# twibby.net
KiCad netlist of a schematic drawn in EasyEDA Pro
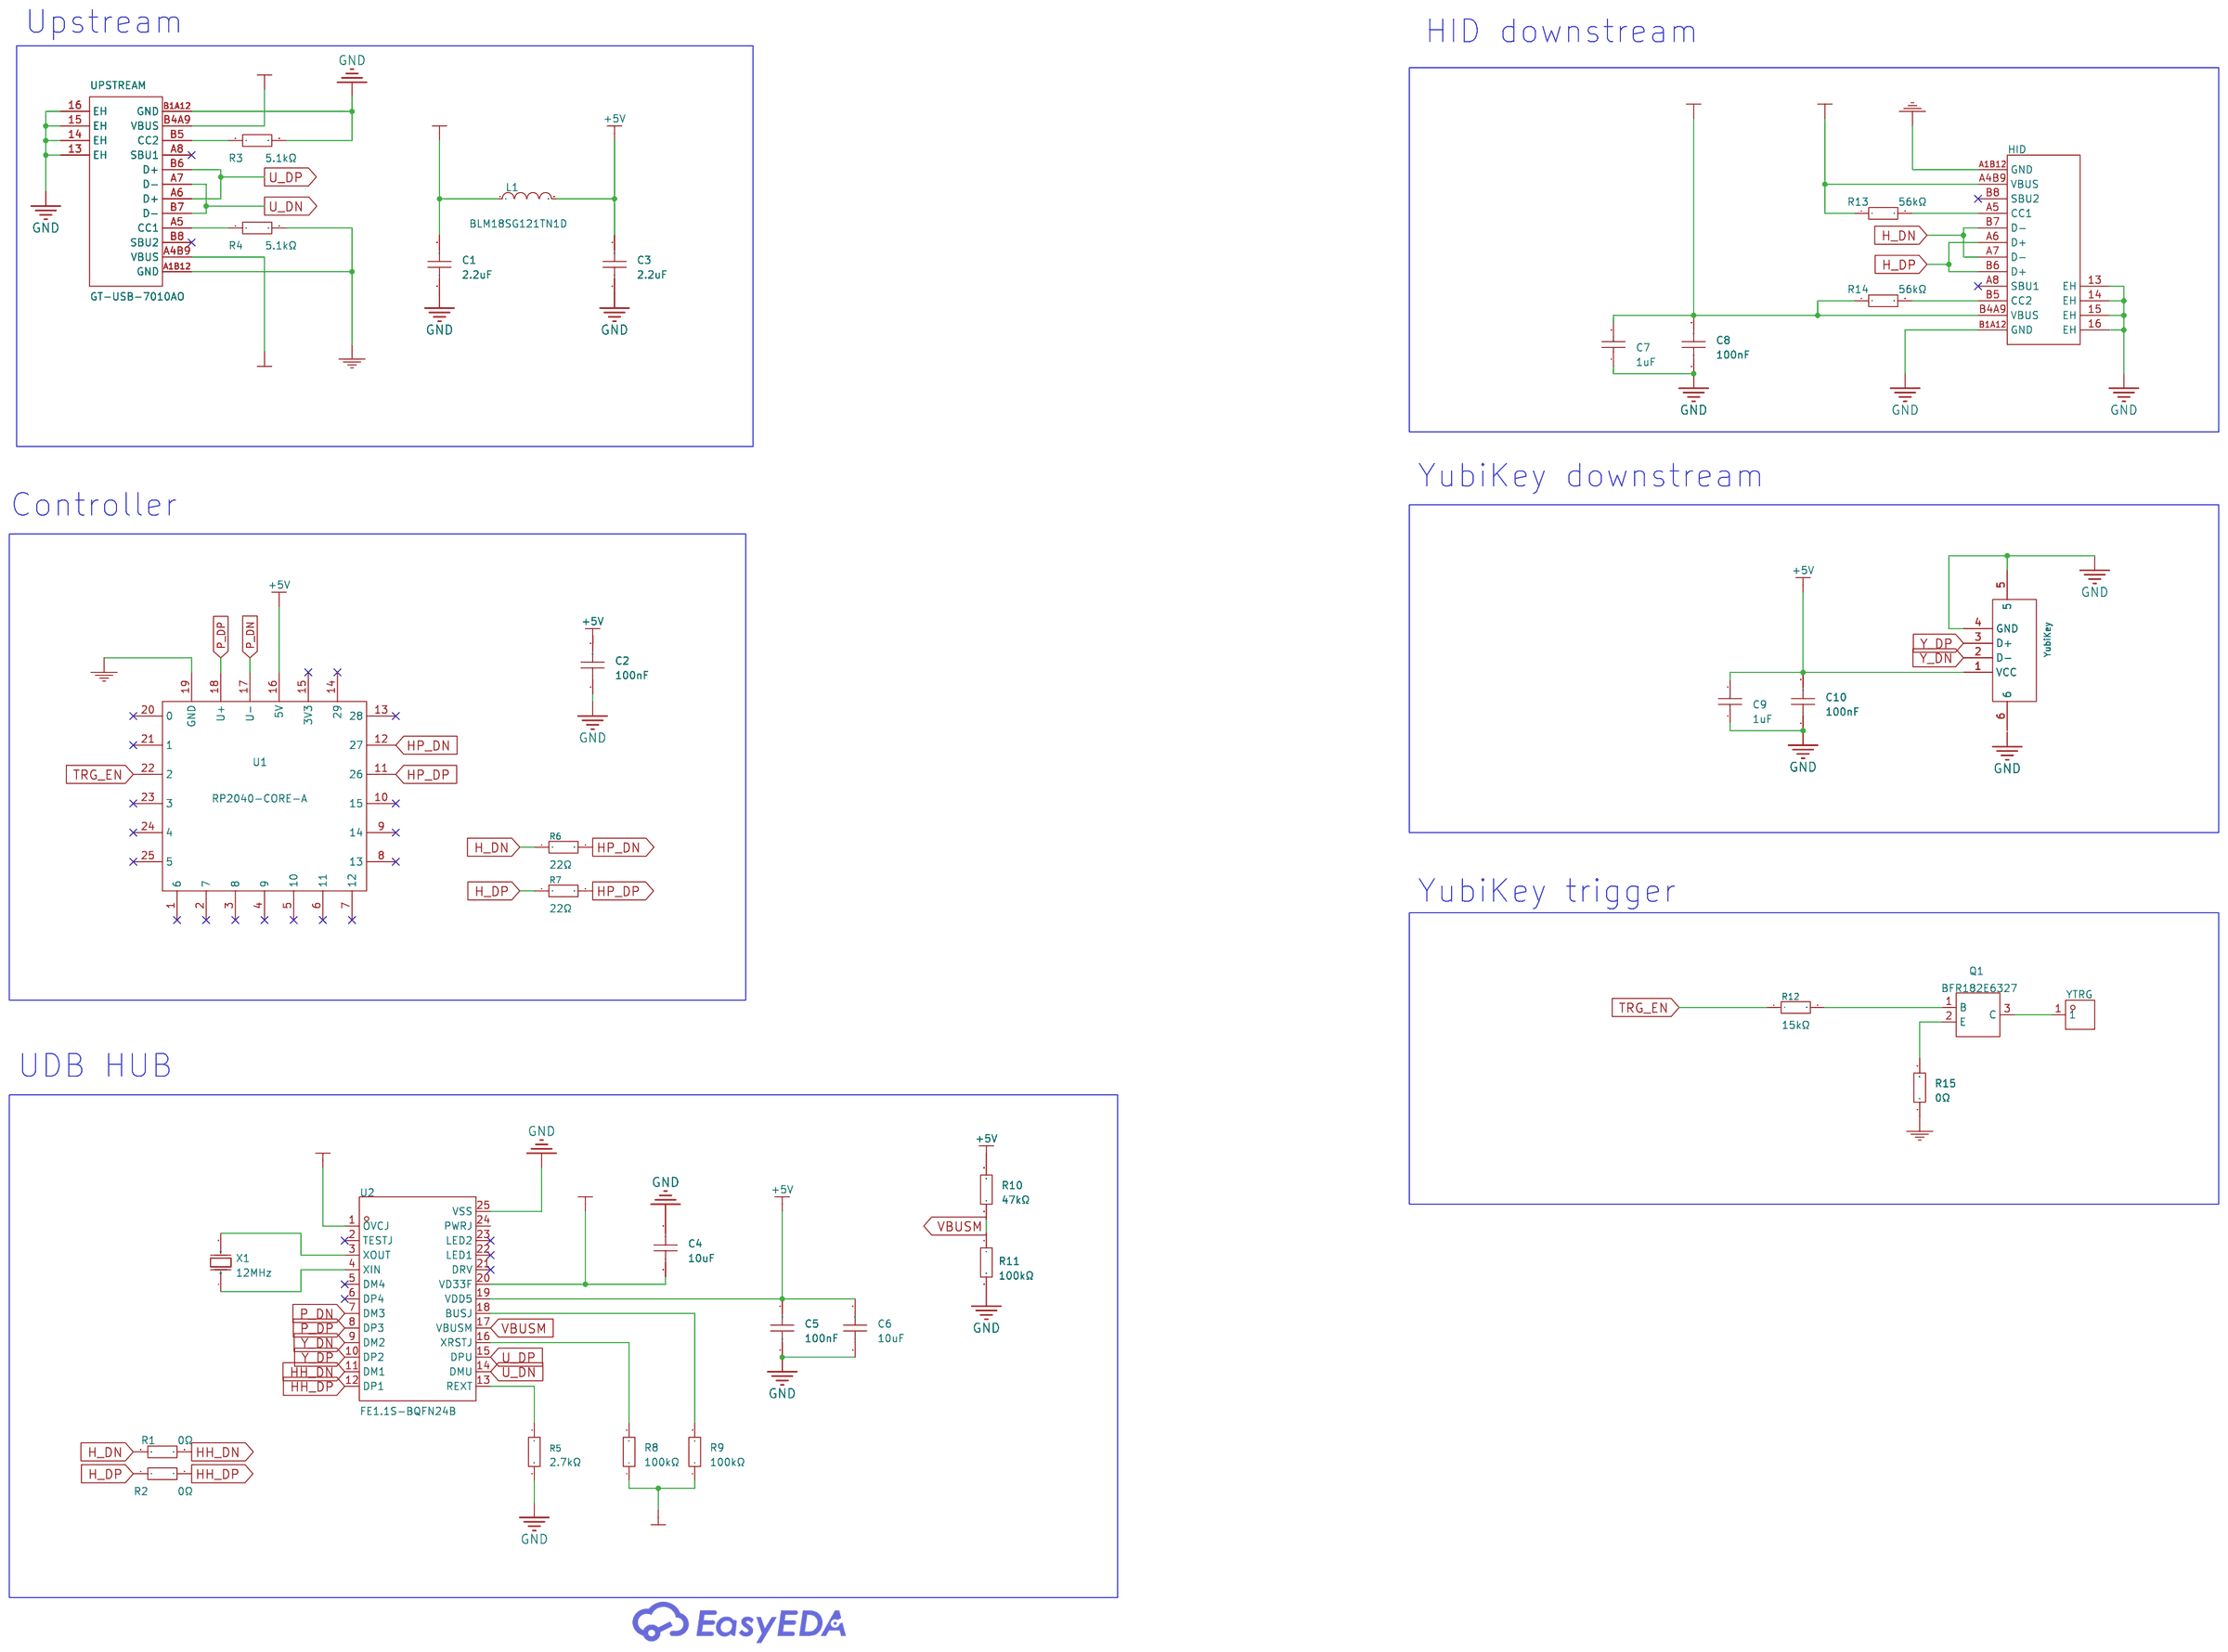
[diagram p0: schematic sheet]

(export (version "E")
  (design (tool "Eeschema 10.0.6"))
  (components
    (comp (ref "C1")
      (value "2.2uF")
      (fields
        (field (name "Manufacturer Part") "CL21A225KBQNNNE")
        (field (name "Manufacturer") "SAMSUNG(三星)")
      )
      (libsource (lib "easyedapro") (part "GRM188Z71E225KE43D"))
    )
    (comp (ref "C2")
      (value "100nF")
      (fields
        (field (name "Manufacturer Part") "CL21B104KCFNNNE")
        (field (name "Manufacturer") "SAMSUNG(三星)")
      )
      (libsource (lib "easyedapro") (part "CL21B104KBFWPJE"))
    )
    (comp (ref "C3")
      (value "2.2uF")
      (fields
        (field (name "Manufacturer Part") "CL21A225KBQNNNE")
        (field (name "Manufacturer") "SAMSUNG(三星)")
      )
      (libsource (lib "easyedapro") (part "GRM188Z71E225KE43D"))
    )
    (comp (ref "C4")
      (value "10uF")
      (footprint "easyedapro:C0603")
      (fields
        (field (name "Manufacturer Part") "CL10A106KP8NNNC")
        (field (name "Manufacturer") "SAMSUNG(三星)")
      )
      (libsource (lib "easyedapro") (part "CL10A106KP8NNNC"))
    )
    (comp (ref "C5")
      (value "100nF")
      (footprint "easyedapro:C0402")
      (fields
        (field (name "Manufacturer Part") "CL05B104KO5NNNC")
        (field (name "Manufacturer") "SAMSUNG(三星)")
      )
      (libsource (lib "easyedapro") (part "100nF"))
    )
    (comp (ref "C6")
      (value "10uF")
      (footprint "easyedapro:C0603")
      (fields
        (field (name "Manufacturer Part") "CL10A106KP8NNNC")
        (field (name "Manufacturer") "SAMSUNG(三星)")
      )
      (libsource (lib "easyedapro") (part "CL10A106KP8NNNC"))
    )
    (comp (ref "C7")
      (value "1uF")
      (description "Capacitance:1uF Tolerance:±10% Tolerance:±10% Voltage Rating:50V Temperature Coefficient:X7R")
      (fields (field (name "Manufacturer Part") "0805B105K500NT") (field (name "Manufacturer") "FH(风华)"))
      (libsource (lib "easyedapro") (part "CL21B105KAFNNNE"))
    )
    (comp (ref "C8")
      (value "100nF")
      (fields
        (field (name "Manufacturer Part") "CL21B104KCFNNNE")
        (field (name "Manufacturer") "SAMSUNG(三星)")
      )
      (libsource (lib "easyedapro") (part "CL21B104KBFWPJE"))
    )
    (comp (ref "C9")
      (value "1uF")
      (description "Capacitance:1uF Tolerance:±10% Tolerance:±10% Voltage Rating:50V Temperature Coefficient:X7R")
      (fields (field (name "Manufacturer Part") "0805B105K500NT") (field (name "Manufacturer") "FH(风华)"))
      (libsource (lib "easyedapro") (part "CL21B105KAFNNNE"))
    )
    (comp (ref "C10")
      (value "100nF")
      (fields
        (field (name "Manufacturer Part") "CL21B104KCFNNNE")
        (field (name "Manufacturer") "SAMSUNG(三星)")
      )
      (libsource (lib "easyedapro") (part "CL21B104KBFWPJE"))
    )
    (comp (ref "HID")
      (value "GT-USB-7010AO")
      (footprint "easyedapro:USB-C-SMD_TYPEC-304J-BCP16")
      (fields (field (name "Manufacturer") "G-Switch(品赞)"))
      (libsource (lib "easyedapro") (part "GT-USB-7010AO"))
    )
    (comp (ref "L1")
      (value "BLM18SG121TN1D")
      (footprint "easyedapro:L0603")
      (fields (field (name "Manufacturer") "muRata(村田)"))
      (libsource (lib "easyedapro") (part "BLM18SG121TN1D"))
    )
    (comp (ref "Q1")
      (value "BFR182E6327")
      (footprint "easyedapro:SOT-23-3_L2.9-W1.3-P1.90-LS2.4-BR")
      (fields (field (name "Manufacturer") "Infineon(英飞凌)") (field (name "Contributor") "LCSC"))
      (libsource (lib "easyedapro") (part "BFR182E6327"))
    )
    (comp (ref "R1")
      (value "0Ω")
      (footprint "easyedapro:R0603")
      (fields
        (field (name "Manufacturer Part") "0603WAF0000T5E")
        (field (name "Manufacturer") "UNI-ROYAL(厚声)")
      )
      (libsource (lib "easyedapro") (part "0603WAF0000T5E"))
    )
    (comp (ref "R2")
      (value "0Ω")
      (footprint "easyedapro:R0603")
      (fields
        (field (name "Manufacturer Part") "0603WAF0000T5E")
        (field (name "Manufacturer") "UNI-ROYAL(厚声)")
      )
      (libsource (lib "easyedapro") (part "0603WAF0000T5E"))
    )
    (comp (ref "R3")
      (value "5.1kΩ")
      (footprint "easyedapro:R0402")
      (fields
        (field (name "Manufacturer Part") "0402WGF5101TCE")
        (field (name "Manufacturer") "UNI-ROYAL(厚声)")
      )
      (libsource (lib "easyedapro") (part "5.1kΩ"))
    )
    (comp (ref "R4")
      (value "5.1kΩ")
      (footprint "easyedapro:R0402")
      (fields
        (field (name "Manufacturer Part") "0402WGF5101TCE")
        (field (name "Manufacturer") "UNI-ROYAL(厚声)")
      )
      (libsource (lib "easyedapro") (part "5.1kΩ"))
    )
    (comp (ref "R5")
      (value "2.7kΩ")
      (fields
        (field (name "Manufacturer Part") "0603WAF2701T5E")
        (field (name "Manufacturer") "UNI-ROYAL(厚声)")
      )
      (libsource (lib "easyedapro") (part "0402WGF2701TCE"))
    )
    (comp (ref "R6")
      (value "22Ω")
      (footprint "easyedapro:R0402")
      (fields
        (field (name "Manufacturer Part") "0402WGF220JTCE")
        (field (name "Manufacturer") "UNI-ROYAL(厚声)")
      )
      (libsource (lib "easyedapro") (part "0402WGF220JTCE"))
    )
    (comp (ref "R7")
      (value "22Ω")
      (footprint "easyedapro:R0402")
      (fields
        (field (name "Manufacturer Part") "0402WGF220JTCE")
        (field (name "Manufacturer") "UNI-ROYAL(厚声)")
      )
      (libsource (lib "easyedapro") (part "0402WGF220JTCE"))
    )
    (comp (ref "R8")
      (value "100kΩ")
      (footprint "easyedapro:R0402")
      (fields
        (field (name "Manufacturer Part") "0402WGF1003TCE")
        (field (name "Manufacturer") "UNI-ROYAL(厚声)")
      )
      (libsource (lib "easyedapro") (part "100kΩ"))
    )
    (comp (ref "R9")
      (value "100kΩ")
      (footprint "easyedapro:R0402")
      (fields
        (field (name "Manufacturer Part") "0402WGF1003TCE")
        (field (name "Manufacturer") "UNI-ROYAL(厚声)")
      )
      (libsource (lib "easyedapro") (part "100kΩ"))
    )
    (comp (ref "R10")
      (value "47kΩ")
      (footprint "easyedapro:R0402")
      (fields
        (field (name "Manufacturer Part") "0402WGF4702TCE")
        (field (name "Manufacturer") "UNI-ROYAL(厚声)")
      )
      (libsource (lib "easyedapro") (part "0402WGF4702TCE"))
    )
    (comp (ref "R11")
      (value "100kΩ")
      (footprint "easyedapro:R0402")
      (fields
        (field (name "Manufacturer Part") "0402WGF1003TCE")
        (field (name "Manufacturer") "UNI-ROYAL(厚声)")
      )
      (libsource (lib "easyedapro") (part "100kΩ"))
    )
    (comp (ref "R12")
      (value "15kΩ")
      (fields
        (field (name "Manufacturer Part") "0603WAF1502T5E")
        (field (name "Manufacturer") "UNI-ROYAL(厚声)")
      )
      (libsource (lib "easyedapro") (part "0402WGF1502TCE"))
    )
    (comp (ref "R13")
      (value "56kΩ")
      (fields
        (field (name "Manufacturer Part") "0603WAF5602T5E")
        (field (name "Manufacturer") "UNI-ROYAL(厚声)")
      )
      (libsource (lib "easyedapro") (part "0402WGF5602TCE"))
    )
    (comp (ref "R14")
      (value "56kΩ")
      (fields
        (field (name "Manufacturer Part") "0603WAF5602T5E")
        (field (name "Manufacturer") "UNI-ROYAL(厚声)")
      )
      (libsource (lib "easyedapro") (part "0402WGF5602TCE"))
    )
    (comp (ref "R15")
      (value "0Ω")
      (footprint "easyedapro:R0603")
      (fields
        (field (name "Manufacturer Part") "0603WAF0000T5E")
        (field (name "Manufacturer") "UNI-ROYAL(厚声)")
      )
      (libsource (lib "easyedapro") (part "0Ω"))
    )
    (comp (ref "U1")
      (value "RP2040-CORE-A")
      (footprint "easyedapro:RP2040-CORE-A")
      (fields (field (name "Contributor") "leeklabsinternational"))
      (libsource (lib "easyedapro") (part "RP2040-CORE-A"))
    )
    (comp (ref "U2")
      (value "FE1.1S-BQFN24B")
      (footprint "easyedapro:WQFN-24_L4.0-W4.0-P0.50-TL-EP2.7")
      (fields (field (name "Manufacturer") "TERMINUS"))
      (libsource (lib "easyedapro") (part "FE1.1S-BQFN24B"))
    )
    (comp (ref "UPSTREAM")
      (value "GT-USB-7010AO")
      (footprint "easyedapro:USB-C-SMD_TYPEC-304J-BCP16")
      (fields (field (name "Manufacturer") "G-Switch(品赞)"))
      (libsource (lib "easyedapro") (part "GT-USB-7010AO"))
    )
    (comp (ref "X1")
      (value "12MHz")
      (footprint "easyedapro:OSC-SMD_L5.0-W3.2")
      (fields (field (name "Manufacturer Part") "TAXM12M2QLFCDT1T") (field (name "Manufacturer") "YJX(雅晶鑫)"))
      (libsource (lib "easyedapro") (part "SMD-5032_2P 12M 20pf 30ppm"))
    )
    (comp (ref "YTRG")
      (value "5017")
      (footprint "easyedapro:CONN-SMD_5017")
      (libsource (lib "easyedapro") (part "5017_C9900015874"))
    )
    (comp (ref "YubiKey")
      (value "912-121A2026S10100")
      (footprint "easyedapro:USB-A-TH_C42425")
      (description "Connector Type:Type-A Standard:USB 2.0 Gender:Female Number of Ports:1 Number of Contacts:4P")
      (fields (field (name "Manufacturer") "精拓金"))
      (libsource (lib "easyedapro") (part "JTJ-USB-AF-90-10.6X13.1-H5.7-002"))
    )
  )
  (nets
    (net (code "1") (name "+3V3") (class "Default")
      (node (ref "C4") (pin "1") (pinfunction "1_1") (pintype "unspecified"))
      (node (ref "R8") (pin "1") (pinfunction "1_1") (pintype "input"))
      (node (ref "R9") (pin "1") (pinfunction "1_1") (pintype "input"))
      (node (ref "U2") (pin "1") (pinfunction "OVCJ_1") (pintype "unspecified"))
      (node (ref "U2") (pin "20") (pinfunction "VD33F_20") (pintype "unspecified"))
    )
    (net (code "2") (name "+5V") (class "Default")
      (node (ref "C10") (pin "2") (pinfunction "2_2") (pintype "unspecified"))
      (node (ref "C2") (pin "2") (pinfunction "2_2") (pintype "unspecified"))
      (node (ref "C3") (pin "2") (pinfunction "2_2") (pintype "unspecified"))
      (node (ref "C5") (pin "2") (pinfunction "2_2") (pintype "unspecified"))
      (node (ref "C6") (pin "2") (pinfunction "2_2") (pintype "unspecified"))
      (node (ref "C7") (pin "2") (pinfunction "2_2") (pintype "input"))
      (node (ref "C8") (pin "2") (pinfunction "2_2") (pintype "unspecified"))
      (node (ref "C9") (pin "2") (pinfunction "2_2") (pintype "input"))
      (node (ref "HID") (pin "A4B9") (pinfunction "VBUS_A4B9") (pintype "unspecified"))
      (node (ref "HID") (pin "B4A9") (pinfunction "VBUS_B4A9") (pintype "unspecified"))
      (node (ref "L1") (pin "2") (pinfunction "2_2") (pintype "input"))
      (node (ref "R10") (pin "2") (pinfunction "2_2") (pintype "input"))
      (node (ref "R13") (pin "1") (pinfunction "1_1") (pintype "input"))
      (node (ref "R14") (pin "1") (pinfunction "1_1") (pintype "input"))
      (node (ref "U1") (pin "16") (pinfunction "5V_16") (pintype "unspecified"))
      (node (ref "U2") (pin "19") (pinfunction "VDD5_19") (pintype "unspecified"))
      (node (ref "YubiKey") (pin "1") (pinfunction "VCC_1") (pintype "input"))
    )
    (net (code "3") (name "+5V_IN") (class "Default")
      (node (ref "C1") (pin "2") (pinfunction "2_2") (pintype "unspecified"))
      (node (ref "L1") (pin "1") (pinfunction "1_1") (pintype "input"))
      (node (ref "UPSTREAM") (pin "A4B9") (pinfunction "VBUS_A4B9") (pintype "unspecified"))
      (node (ref "UPSTREAM") (pin "B4A9") (pinfunction "VBUS_B4A9") (pintype "unspecified"))
    )
    (net (code "4") (name "GND") (class "Default")
      (node (ref "C1") (pin "1") (pinfunction "1_1") (pintype "unspecified"))
      (node (ref "C10") (pin "1") (pinfunction "1_1") (pintype "unspecified"))
      (node (ref "C2") (pin "1") (pinfunction "1_1") (pintype "unspecified"))
      (node (ref "C3") (pin "1") (pinfunction "1_1") (pintype "unspecified"))
      (node (ref "C4") (pin "2") (pinfunction "2_2") (pintype "unspecified"))
      (node (ref "C5") (pin "1") (pinfunction "1_1") (pintype "unspecified"))
      (node (ref "C6") (pin "1") (pinfunction "1_1") (pintype "unspecified"))
      (node (ref "C7") (pin "1") (pinfunction "1_1") (pintype "input"))
      (node (ref "C8") (pin "1") (pinfunction "1_1") (pintype "unspecified"))
      (node (ref "C9") (pin "1") (pinfunction "1_1") (pintype "input"))
      (node (ref "HID") (pin "13") (pinfunction "EH_13") (pintype "unspecified"))
      (node (ref "HID") (pin "14") (pinfunction "EH_14") (pintype "unspecified"))
      (node (ref "HID") (pin "15") (pinfunction "EH_15") (pintype "unspecified"))
      (node (ref "HID") (pin "16") (pinfunction "EH_16") (pintype "unspecified"))
      (node (ref "HID") (pin "A1B12") (pinfunction "GND_A1B12") (pintype "unspecified"))
      (node (ref "HID") (pin "B1A12") (pinfunction "GND_B1A12") (pintype "unspecified"))
      (node (ref "R11") (pin "2") (pinfunction "2_2") (pintype "input"))
      (node (ref "R15") (pin "1") (pinfunction "1_1") (pintype "input"))
      (node (ref "R3") (pin "2") (pinfunction "2_2") (pintype "input"))
      (node (ref "R4") (pin "2") (pinfunction "2_2") (pintype "input"))
      (node (ref "R5") (pin "2") (pinfunction "2_2") (pintype "input"))
      (node (ref "U1") (pin "19") (pinfunction "GND_19") (pintype "unspecified"))
      (node (ref "U2") (pin "25") (pinfunction "VSS_25") (pintype "unspecified"))
      (node (ref "UPSTREAM") (pin "13") (pinfunction "EH_13") (pintype "unspecified"))
      (node (ref "UPSTREAM") (pin "14") (pinfunction "EH_14") (pintype "unspecified"))
      (node (ref "UPSTREAM") (pin "15") (pinfunction "EH_15") (pintype "unspecified"))
      (node (ref "UPSTREAM") (pin "16") (pinfunction "EH_16") (pintype "unspecified"))
      (node (ref "UPSTREAM") (pin "A1B12") (pinfunction "GND_A1B12") (pintype "unspecified"))
      (node (ref "UPSTREAM") (pin "B1A12") (pinfunction "GND_B1A12") (pintype "unspecified"))
      (node (ref "YubiKey") (pin "4") (pinfunction "GND_4") (pintype "input"))
      (node (ref "YubiKey") (pin "5") (pinfunction "5_5") (pintype "input"))
    )
    (net (code "5") (name "HH_DN") (class "Default")
      (node (ref "R1") (pin "2") (pinfunction "2_2") (pintype "input"))
      (node (ref "U2") (pin "11") (pinfunction "DM1_11") (pintype "unspecified"))
    )
    (net (code "6") (name "HH_DP") (class "Default")
      (node (ref "R2") (pin "2") (pinfunction "2_2") (pintype "input"))
      (node (ref "U2") (pin "12") (pinfunction "DP1_12") (pintype "unspecified"))
    )
    (net (code "7") (name "HP_DN") (class "Default")
      (node (ref "R6") (pin "2") (pinfunction "2_2") (pintype "input"))
      (node (ref "U1") (pin "12") (pinfunction "27_12") (pintype "unspecified"))
    )
    (net (code "8") (name "HP_DP") (class "Default")
      (node (ref "R7") (pin "2") (pinfunction "2_2") (pintype "input"))
      (node (ref "U1") (pin "11") (pinfunction "26_11") (pintype "unspecified"))
    )
    (net (code "9") (name "H_DN") (class "Default")
      (node (ref "HID") (pin "A7") (pinfunction "D-_A7") (pintype "unspecified"))
      (node (ref "HID") (pin "B7") (pinfunction "D-_B7") (pintype "unspecified"))
      (node (ref "R1") (pin "1") (pinfunction "1_1") (pintype "input"))
      (node (ref "R6") (pin "1") (pinfunction "1_1") (pintype "input"))
    )
    (net (code "10") (name "H_DP") (class "Default")
      (node (ref "HID") (pin "A6") (pinfunction "D+_A6") (pintype "unspecified"))
      (node (ref "HID") (pin "B6") (pinfunction "D+_B6") (pintype "unspecified"))
      (node (ref "R2") (pin "1") (pinfunction "1_1") (pintype "input"))
      (node (ref "R7") (pin "1") (pinfunction "1_1") (pintype "input"))
    )
    (net (code "11") (name "Net-(HID-CC1)") (class "Default")
      (node (ref "HID") (pin "A5") (pinfunction "CC1_A5") (pintype "unspecified"))
      (node (ref "R13") (pin "2") (pinfunction "2_2") (pintype "input"))
    )
    (net (code "12") (name "Net-(HID-CC2)") (class "Default")
      (node (ref "HID") (pin "B5") (pinfunction "CC2_B5") (pintype "unspecified"))
      (node (ref "R14") (pin "2") (pinfunction "2_2") (pintype "input"))
    )
    (net (code "13") (name "Net-(Q1-B)") (class "Default")
      (node (ref "Q1") (pin "1") (pinfunction "B_1") (pintype "unspecified"))
      (node (ref "R12") (pin "2") (pinfunction "2_2") (pintype "input"))
    )
    (net (code "14") (name "Net-(Q1-C)") (class "Default")
      (node (ref "Q1") (pin "3") (pinfunction "C_3") (pintype "unspecified"))
      (node (ref "YTRG") (pin "1") (pinfunction "1_1") (pintype "unspecified"))
    )
    (net (code "15") (name "Net-(Q1-E)") (class "Default")
      (node (ref "Q1") (pin "2") (pinfunction "E_2") (pintype "unspecified"))
      (node (ref "R15") (pin "2") (pinfunction "2_2") (pintype "input"))
    )
    (net (code "16") (name "Net-(U2-BUSJ)") (class "Default")
      (node (ref "R9") (pin "2") (pinfunction "2_2") (pintype "input"))
      (node (ref "U2") (pin "18") (pinfunction "BUSJ_18") (pintype "unspecified"))
    )
    (net (code "17") (name "Net-(U2-REXT)") (class "Default")
      (node (ref "R5") (pin "1") (pinfunction "1_1") (pintype "input"))
      (node (ref "U2") (pin "13") (pinfunction "REXT_13") (pintype "unspecified"))
    )
    (net (code "18") (name "Net-(U2-XIN)") (class "Default")
      (node (ref "U2") (pin "4") (pinfunction "XIN_4") (pintype "unspecified"))
      (node (ref "X1") (pin "1") (pinfunction "OSC1_1") (pintype "input"))
    )
    (net (code "19") (name "Net-(U2-XOUT)") (class "Default")
      (node (ref "U2") (pin "3") (pinfunction "XOUT_3") (pintype "unspecified"))
      (node (ref "X1") (pin "2") (pinfunction "OSC2_2") (pintype "input"))
    )
    (net (code "20") (name "Net-(U2-XRSTJ)") (class "Default")
      (node (ref "R8") (pin "2") (pinfunction "2_2") (pintype "input"))
      (node (ref "U2") (pin "16") (pinfunction "XRSTJ_16") (pintype "unspecified"))
    )
    (net (code "21") (name "Net-(UPSTREAM-CC1)") (class "Default")
      (node (ref "R4") (pin "1") (pinfunction "1_1") (pintype "input"))
      (node (ref "UPSTREAM") (pin "A5") (pinfunction "CC1_A5") (pintype "unspecified"))
    )
    (net (code "22") (name "Net-(UPSTREAM-CC2)") (class "Default")
      (node (ref "R3") (pin "1") (pinfunction "1_1") (pintype "input"))
      (node (ref "UPSTREAM") (pin "B5") (pinfunction "CC2_B5") (pintype "unspecified"))
    )
    (net (code "23") (name "P_DN") (class "Default")
      (node (ref "U1") (pin "17") (pinfunction "U-_17") (pintype "unspecified"))
      (node (ref "U2") (pin "7") (pinfunction "DM3_7") (pintype "unspecified"))
    )
    (net (code "24") (name "P_DP") (class "Default")
      (node (ref "U1") (pin "18") (pinfunction "U+_18") (pintype "unspecified"))
      (node (ref "U2") (pin "8") (pinfunction "DP3_8") (pintype "unspecified"))
    )
    (net (code "25") (name "TRG_EN") (class "Default")
      (node (ref "R12") (pin "1") (pinfunction "1_1") (pintype "input"))
      (node (ref "U1") (pin "22") (pinfunction "2_22") (pintype "unspecified"))
    )
    (net (code "26") (name "U_DN") (class "Default")
      (node (ref "U2") (pin "14") (pinfunction "DMU_14") (pintype "unspecified"))
      (node (ref "UPSTREAM") (pin "A7") (pinfunction "D-_A7") (pintype "unspecified"))
      (node (ref "UPSTREAM") (pin "B7") (pinfunction "D-_B7") (pintype "unspecified"))
    )
    (net (code "27") (name "U_DP") (class "Default")
      (node (ref "U2") (pin "15") (pinfunction "DPU_15") (pintype "unspecified"))
      (node (ref "UPSTREAM") (pin "A6") (pinfunction "D+_A6") (pintype "unspecified"))
      (node (ref "UPSTREAM") (pin "B6") (pinfunction "D+_B6") (pintype "unspecified"))
    )
    (net (code "28") (name "VBUSM") (class "Default")
      (node (ref "R10") (pin "1") (pinfunction "1_1") (pintype "input"))
      (node (ref "R11") (pin "1") (pinfunction "1_1") (pintype "input"))
      (node (ref "U2") (pin "17") (pinfunction "VBUSM_17") (pintype "unspecified"))
    )
    (net (code "29") (name "Y_DN") (class "Default")
      (node (ref "U2") (pin "9") (pinfunction "DM2_9") (pintype "unspecified"))
      (node (ref "YubiKey") (pin "2") (pinfunction "D-_2") (pintype "input"))
    )
    (net (code "30") (name "Y_DP") (class "Default")
      (node (ref "U2") (pin "10") (pinfunction "DP2_10") (pintype "unspecified"))
      (node (ref "YubiKey") (pin "3") (pinfunction "D+_3") (pintype "input"))
    )
    (net (code "31") (name "unconnected-(HID-SBU1-PadA8)") (class "Default")
      (node (ref "HID") (pin "A8") (pinfunction "SBU1_A8") (pintype "unspecified+no_connect"))
    )
    (net (code "32") (name "unconnected-(HID-SBU2-PadB8)") (class "Default")
      (node (ref "HID") (pin "B8") (pinfunction "SBU2_B8") (pintype "unspecified+no_connect"))
    )
    (net (code "33") (name "unconnected-(U1-0-Pad20)") (class "Default")
      (node (ref "U1") (pin "20") (pinfunction "0_20") (pintype "unspecified+no_connect"))
    )
    (net (code "34") (name "unconnected-(U1-1-Pad21)") (class "Default")
      (node (ref "U1") (pin "21") (pinfunction "1_21") (pintype "unspecified+no_connect"))
    )
    (net (code "35") (name "unconnected-(U1-3-Pad23)") (class "Default")
      (node (ref "U1") (pin "23") (pinfunction "3_23") (pintype "unspecified+no_connect"))
    )
    (net (code "36") (name "unconnected-(U1-3V3-Pad15)") (class "Default")
      (node (ref "U1") (pin "15") (pinfunction "3V3_15") (pintype "unspecified+no_connect"))
    )
    (net (code "37") (name "unconnected-(U1-4-Pad24)") (class "Default")
      (node (ref "U1") (pin "24") (pinfunction "4_24") (pintype "unspecified+no_connect"))
    )
    (net (code "38") (name "unconnected-(U1-5-Pad25)") (class "Default")
      (node (ref "U1") (pin "25") (pinfunction "5_25") (pintype "unspecified+no_connect"))
    )
    (net (code "39") (name "unconnected-(U1-6-Pad1)") (class "Default")
      (node (ref "U1") (pin "1") (pinfunction "6_1") (pintype "unspecified+no_connect"))
    )
    (net (code "40") (name "unconnected-(U1-7-Pad2)") (class "Default")
      (node (ref "U1") (pin "2") (pinfunction "7_2") (pintype "unspecified+no_connect"))
    )
    (net (code "41") (name "unconnected-(U1-8-Pad3)") (class "Default")
      (node (ref "U1") (pin "3") (pinfunction "8_3") (pintype "unspecified+no_connect"))
    )
    (net (code "42") (name "unconnected-(U1-9-Pad4)") (class "Default")
      (node (ref "U1") (pin "4") (pinfunction "9_4") (pintype "unspecified+no_connect"))
    )
    (net (code "43") (name "unconnected-(U1-10-Pad5)") (class "Default")
      (node (ref "U1") (pin "5") (pinfunction "10_5") (pintype "unspecified+no_connect"))
    )
    (net (code "44") (name "unconnected-(U1-11-Pad6)") (class "Default")
      (node (ref "U1") (pin "6") (pinfunction "11_6") (pintype "unspecified+no_connect"))
    )
    (net (code "45") (name "unconnected-(U1-12-Pad7)") (class "Default")
      (node (ref "U1") (pin "7") (pinfunction "12_7") (pintype "unspecified+no_connect"))
    )
    (net (code "46") (name "unconnected-(U1-13-Pad8)") (class "Default")
      (node (ref "U1") (pin "8") (pinfunction "13_8") (pintype "unspecified+no_connect"))
    )
    (net (code "47") (name "unconnected-(U1-14-Pad9)") (class "Default")
      (node (ref "U1") (pin "9") (pinfunction "14_9") (pintype "unspecified+no_connect"))
    )
    (net (code "48") (name "unconnected-(U1-15-Pad10)") (class "Default")
      (node (ref "U1") (pin "10") (pinfunction "15_10") (pintype "unspecified+no_connect"))
    )
    (net (code "49") (name "unconnected-(U1-28-Pad13)") (class "Default")
      (node (ref "U1") (pin "13") (pinfunction "28_13") (pintype "unspecified+no_connect"))
    )
    (net (code "50") (name "unconnected-(U1-29-Pad14)") (class "Default")
      (node (ref "U1") (pin "14") (pinfunction "29_14") (pintype "unspecified+no_connect"))
    )
    (net (code "51") (name "unconnected-(U2-DM4-Pad5)") (class "Default")
      (node (ref "U2") (pin "5") (pinfunction "DM4_5") (pintype "unspecified+no_connect"))
    )
    (net (code "52") (name "unconnected-(U2-DP4-Pad6)") (class "Default")
      (node (ref "U2") (pin "6") (pinfunction "DP4_6") (pintype "unspecified+no_connect"))
    )
    (net (code "53") (name "unconnected-(U2-DRV-Pad21)") (class "Default")
      (node (ref "U2") (pin "21") (pinfunction "DRV_21") (pintype "unspecified+no_connect"))
    )
    (net (code "54") (name "unconnected-(U2-LED1-Pad22)") (class "Default")
      (node (ref "U2") (pin "22") (pinfunction "LED1_22") (pintype "unspecified+no_connect"))
    )
    (net (code "55") (name "unconnected-(U2-LED2-Pad23)") (class "Default")
      (node (ref "U2") (pin "23") (pinfunction "LED2_23") (pintype "unspecified+no_connect"))
    )
    (net (code "56") (name "unconnected-(U2-PWRJ-Pad24)") (class "Default")
      (node (ref "U2") (pin "24") (pinfunction "PWRJ_24") (pintype "unspecified"))
    )
    (net (code "57") (name "unconnected-(U2-TESTJ-Pad2)") (class "Default")
      (node (ref "U2") (pin "2") (pinfunction "TESTJ_2") (pintype "unspecified+no_connect"))
    )
    (net (code "58") (name "unconnected-(UPSTREAM-SBU1-PadA8)") (class "Default")
      (node (ref "UPSTREAM") (pin "A8") (pinfunction "SBU1_A8") (pintype "unspecified+no_connect"))
    )
    (net (code "59") (name "unconnected-(UPSTREAM-SBU2-PadB8)") (class "Default")
      (node (ref "UPSTREAM") (pin "B8") (pinfunction "SBU2_B8") (pintype "unspecified+no_connect"))
    )
    (net (code "60") (name "unconnected-(YubiKey-Pad6)") (class "Default")
      (node (ref "YubiKey") (pin "6") (pinfunction "6_6") (pintype "input"))
    )
  )
)
